# ISO_PWR_UCC12040DVER.net
KiCad netlist of a schematic drawn in Altium Designer
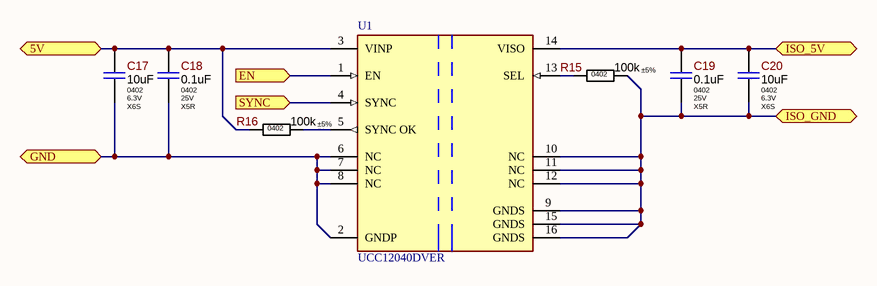
[diagram p0: ISO_PWR_UCC12040DVER.SchDoc]

(export (version "E")
  (design (tool "Eeschema 10.0.6"))
  (components
    (comp (ref "C17")
      (value "10uF")
      (footprint "C_CERAMIC_0402_MED")
      (description "10uF 6.3V X6S ±20% 0402 Ceramic Capacitor RoHS")
      (fields
        (field (name "PACKAGE") "0402")
        (field (name "VOLTAGE") "6.3V")
        (field (name "DIELECTRIC TYPE") "X6S")
        (field (name "PART NUMBER") "GRM155C80J106ME11D")
        (field (name "MANUFACTURER") "Murata Electronics")
      )
      (libsource (lib "EL.XXX.T01") (part "Capacitor-NonPolar"))
    )
    (comp (ref "C18")
      (value "0.1uF")
      (footprint "C_CERAMIC_0402_MED")
      (description "100nF 25V X5R ±10% 0402 Ceramic Capacitor RoHS")
      (fields
        (field (name "PACKAGE") "0402")
        (field (name "VOLTAGE") "25V")
        (field (name "DIELECTRIC TYPE") "X5R")
        (field (name "PART NUMBER") "CL05A104KA5NNNC")
        (field (name "MANUFACTURER") "Samsung Electro-Mechanics")
      )
      (libsource (lib "EL.XXX.T01") (part "Capacitor-NonPolar"))
    )
    (comp (ref "C19")
      (value "0.1uF")
      (footprint "C_CERAMIC_0402_MED")
      (description "100nF 25V X5R ±10% 0402 Ceramic Capacitor RoHS")
      (fields
        (field (name "PACKAGE") "0402")
        (field (name "VOLTAGE") "25V")
        (field (name "DIELECTRIC TYPE") "X5R")
        (field (name "PART NUMBER") "CL05A104KA5NNNC")
        (field (name "MANUFACTURER") "Samsung Electro-Mechanics")
      )
      (libsource (lib "EL.XXX.T01") (part "Capacitor-NonPolar"))
    )
    (comp (ref "C20")
      (value "10uF")
      (footprint "C_CERAMIC_0402_MED")
      (description "10uF 6.3V X6S ±20% 0402 Ceramic Capacitor RoHS")
      (fields
        (field (name "PACKAGE") "0402")
        (field (name "VOLTAGE") "6.3V")
        (field (name "DIELECTRIC TYPE") "X6S")
        (field (name "PART NUMBER") "GRM155C80J106ME11D")
        (field (name "MANUFACTURER") "Murata Electronics")
      )
      (libsource (lib "EL.XXX.T01") (part "Capacitor-NonPolar"))
    )
    (comp (ref "R15")
      (value "100k")
      (footprint "R_ANY_CHIP_0402_HI")
      (description "100 kOhms ±5% 1/16W 0402 Thick Film Resistor")
      (fields
        (field (name "TOLERANCE") "±5%")
        (field (name "PACKAGE") "0402")
        (field (name "PART NUMBER") "RC0402JR-07100KL")
        (field (name "MANUFACTURER") "Yageo")
      )
      (libsource (lib "EL.XXX.T01") (part "Resistor"))
    )
    (comp (ref "R16")
      (value "100k")
      (footprint "R_ANY_CHIP_0402_HI")
      (description "100 kOhms ±5% 1/16W 0402 Thick Film Resistor")
      (fields
        (field (name "TOLERANCE") "±5%")
        (field (name "PACKAGE") "0402")
        (field (name "PART NUMBER") "RC0402JR-07100KL")
        (field (name "MANUFACTURER") "Yageo")
      )
      (libsource (lib "EL.XXX.T01") (part "Resistor"))
    )
    (comp (ref "U1")
      (value "UCC12040DVER")
      (footprint "FP-DVE0016A-MFG")
      (description "DC DC CONVERTER 5V 500mW")
      (libsource (lib "EL.XXX.T01") (part "CMP-04910-000064-1"))
    )
  )
  (nets
    (net (code "1") (name "/5V") (class "Default")
      (node (ref "C17") (pin "1") (pinfunction "1_1") (pintype "passive"))
      (node (ref "C18") (pin "1") (pinfunction "1_1") (pintype "passive"))
      (node (ref "R16") (pin "1") (pintype "passive"))
      (node (ref "U1") (pin "3") (pinfunction "VINP_3") (pintype "power_in"))
    )
    (net (code "2") (name "/EN") (class "Default")
      (node (ref "U1") (pin "1") (pinfunction "EN_1") (pintype "input"))
    )
    (net (code "3") (name "/GND") (class "Default")
      (node (ref "C17") (pin "2") (pinfunction "2_2") (pintype "passive"))
      (node (ref "C18") (pin "2") (pinfunction "2_2") (pintype "passive"))
      (node (ref "U1") (pin "2") (pinfunction "GNDP_2") (pintype "power_in"))
      (node (ref "U1") (pin "6") (pinfunction "NC_6") (pintype "passive"))
      (node (ref "U1") (pin "7") (pinfunction "NC_7") (pintype "passive"))
      (node (ref "U1") (pin "8") (pinfunction "NC_8") (pintype "passive"))
    )
    (net (code "4") (name "/ISO_5V") (class "Default")
      (node (ref "C19") (pin "1") (pinfunction "1_1") (pintype "passive"))
      (node (ref "C20") (pin "1") (pinfunction "1_1") (pintype "passive"))
      (node (ref "U1") (pin "14") (pinfunction "VISO_14") (pintype "power_in"))
    )
    (net (code "5") (name "/ISO_GND") (class "Default")
      (node (ref "C19") (pin "2") (pinfunction "2_2") (pintype "passive"))
      (node (ref "C20") (pin "2") (pinfunction "2_2") (pintype "passive"))
      (node (ref "R15") (pin "2") (pintype "passive"))
      (node (ref "U1") (pin "10") (pinfunction "NC_10") (pintype "passive"))
      (node (ref "U1") (pin "11") (pinfunction "NC_11") (pintype "passive"))
      (node (ref "U1") (pin "12") (pinfunction "NC_12") (pintype "passive"))
      (node (ref "U1") (pin "15") (pinfunction "GNDS_15") (pintype "power_in"))
      (node (ref "U1") (pin "16") (pinfunction "GNDS_16") (pintype "power_in"))
      (node (ref "U1") (pin "9") (pinfunction "GNDS_9") (pintype "power_in"))
    )
    (net (code "6") (name "/SYNC") (class "Default")
      (node (ref "U1") (pin "4") (pinfunction "SYNC_4") (pintype "input"))
    )
    (net (code "7") (name "Net-(U1-SEL)") (class "Default")
      (node (ref "R15") (pin "1") (pintype "passive"))
      (node (ref "U1") (pin "13") (pinfunction "SEL_13") (pintype "input"))
    )
    (net (code "8") (name "Net-(U1-SYNC_OK)") (class "Default")
      (node (ref "R16") (pin "2") (pintype "passive"))
      (node (ref "U1") (pin "5") (pinfunction "SYNC_OK_5") (pintype "output"))
    )
  )
)
